# altuamSTM32_schematic.net
KiCad netlist of a schematic drawn in Altium Designer
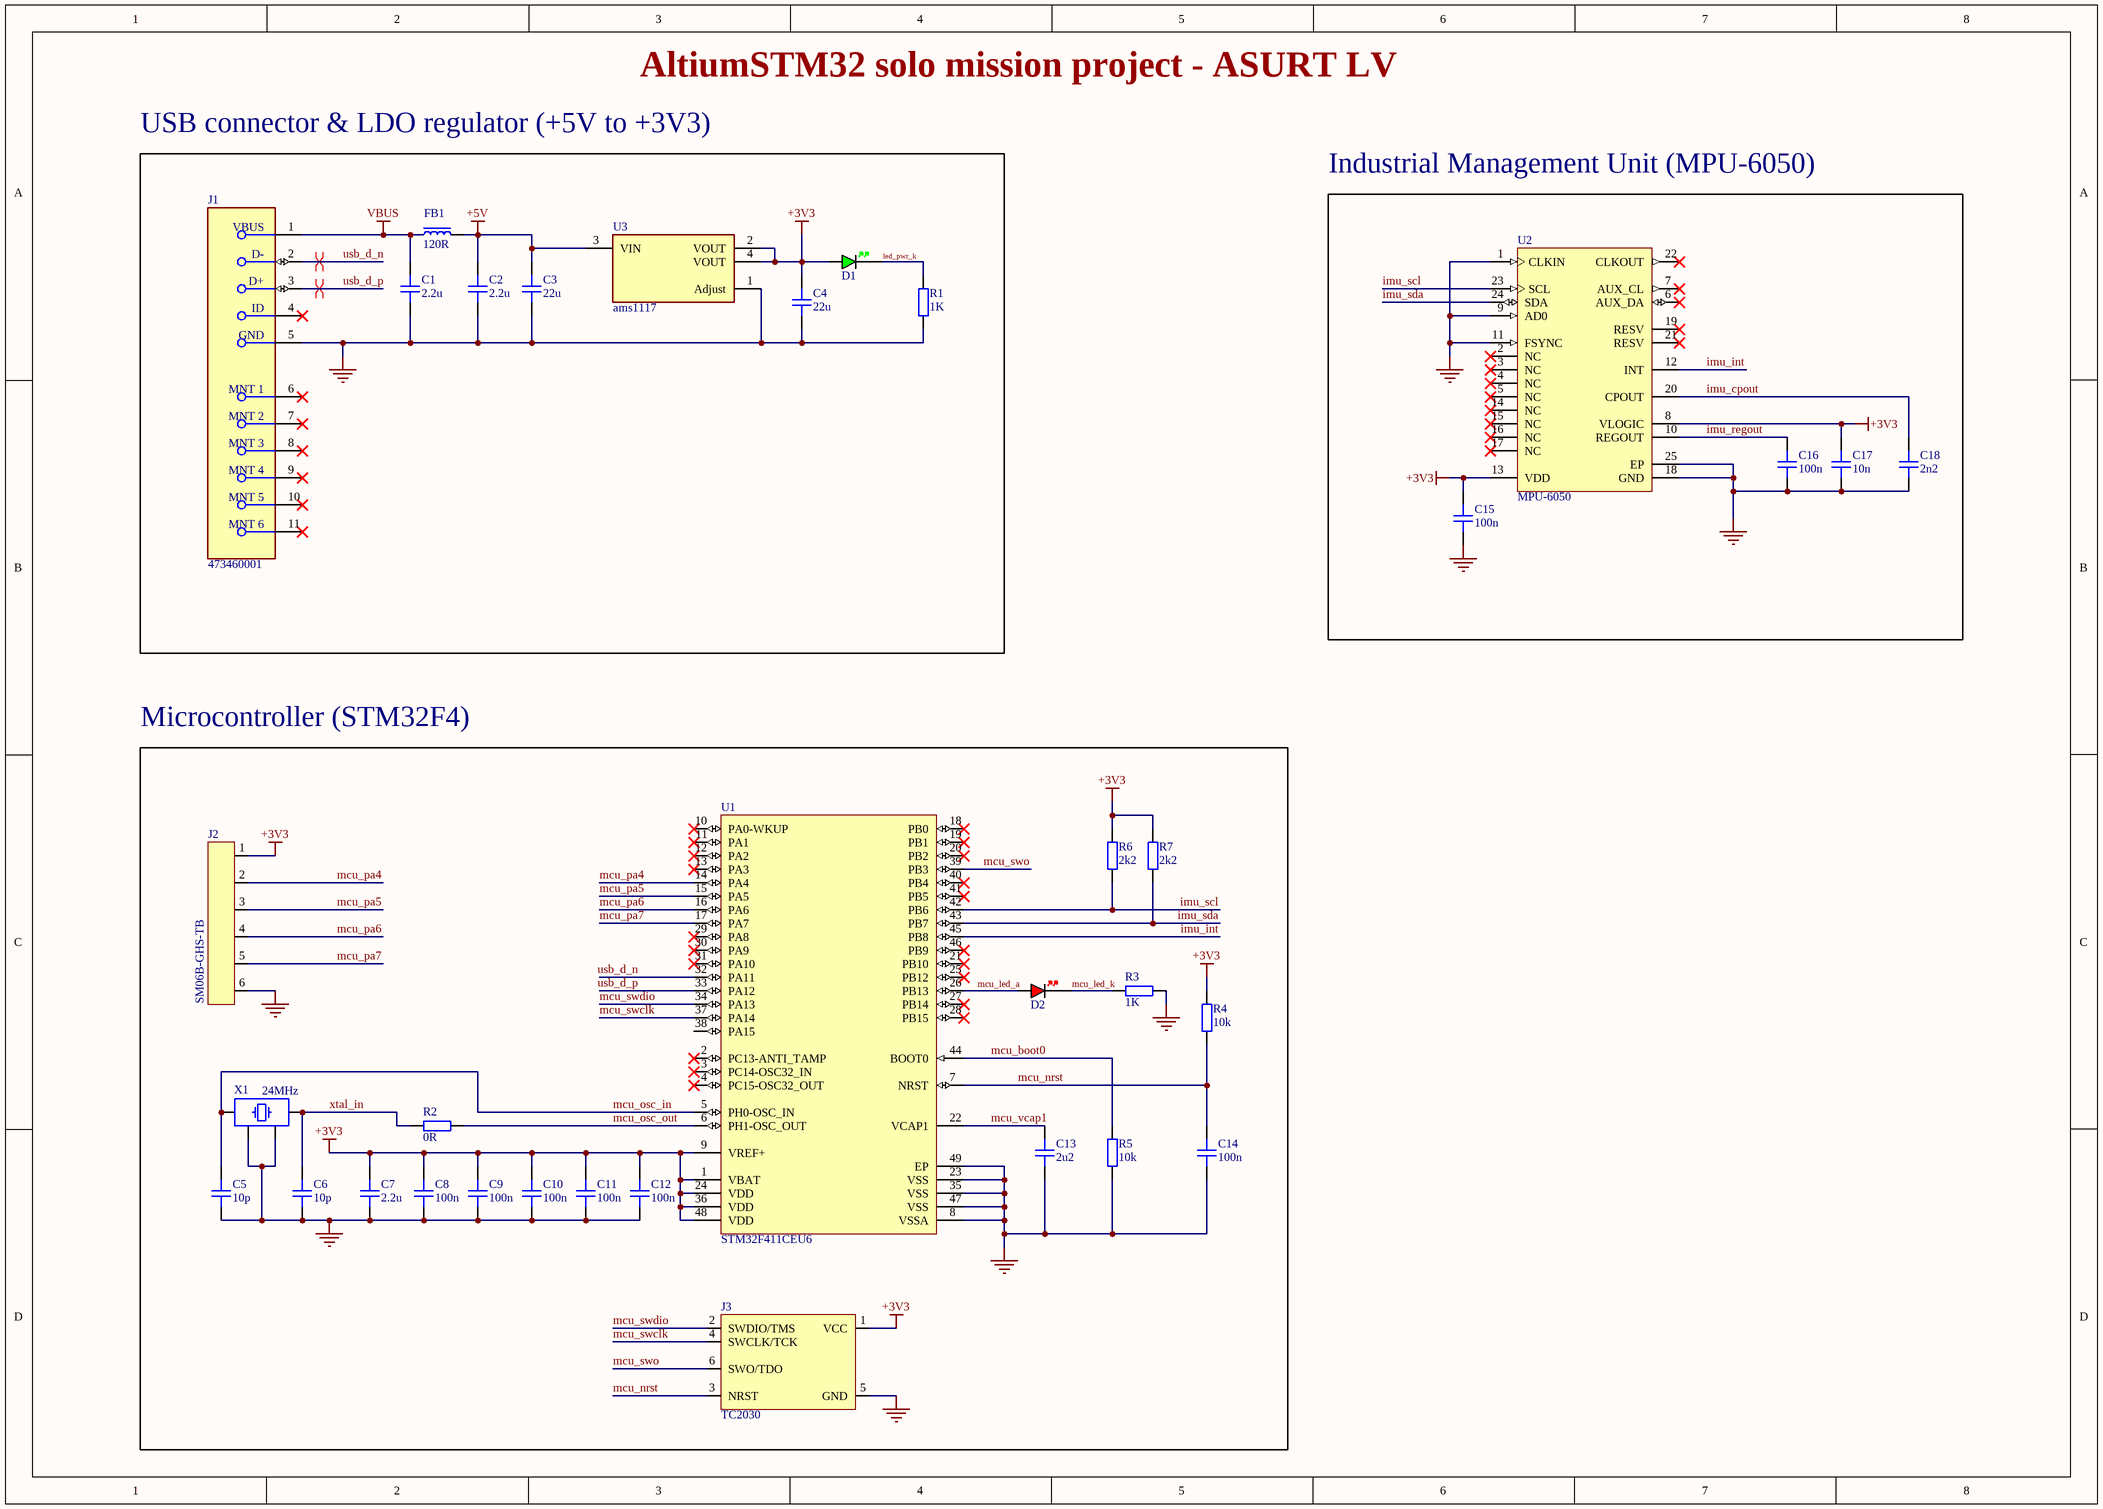
[diagram p0: altuamSTM32_schematic.SchDoc]

(export (version "E")
  (design (tool "Eeschema 10.0.6"))
  (components
    (comp (ref "C1")
      (value "2.2u")
      (footprint "CAP_0603")
      (description "Capacitor SMD 0603")
      (libsource (lib "Schematic-Lib-PhilsLab") (part "CAP_0603"))
    )
    (comp (ref "C2")
      (value "2.2u")
      (footprint "CAP_0603")
      (description "Capacitor SMD 0603")
      (libsource (lib "Schematic-Lib-PhilsLab") (part "CAP_0603"))
    )
    (comp (ref "C3")
      (value "22u")
      (footprint "CAP_0805")
      (description "Capacitor SMD 0805")
      (libsource (lib "Schematic-Lib-PhilsLab") (part "CAP_0805"))
    )
    (comp (ref "C4")
      (value "22u")
      (footprint "CAP_0805")
      (description "Capacitor SMD 0805")
      (libsource (lib "Schematic-Lib-PhilsLab") (part "CAP_0805"))
    )
    (comp (ref "C5")
      (value "10p")
      (footprint "CAP_0402")
      (description "Capacitor SMD 0402")
      (libsource (lib "Schematic-Lib-PhilsLab") (part "CAP_0402"))
    )
    (comp (ref "C6")
      (value "10p")
      (footprint "CAP_0402")
      (description "Capacitor SMD 0402")
      (libsource (lib "Schematic-Lib-PhilsLab") (part "CAP_0402"))
    )
    (comp (ref "C7")
      (value "2.2u")
      (footprint "CAP_0603")
      (description "Capacitor SMD 0603")
      (libsource (lib "Schematic-Lib-PhilsLab") (part "CAP_0603"))
    )
    (comp (ref "C8")
      (value "100n")
      (footprint "CAP_0402")
      (description "Capacitor SMD 0402")
      (libsource (lib "Schematic-Lib-PhilsLab") (part "CAP_0402"))
    )
    (comp (ref "C9")
      (value "100n")
      (footprint "CAP_0402")
      (description "Capacitor SMD 0402")
      (libsource (lib "Schematic-Lib-PhilsLab") (part "CAP_0402"))
    )
    (comp (ref "C10")
      (value "100n")
      (footprint "CAP_0402")
      (description "Capacitor SMD 0402")
      (libsource (lib "Schematic-Lib-PhilsLab") (part "CAP_0402"))
    )
    (comp (ref "C11")
      (value "100n")
      (footprint "CAP_0402")
      (description "Capacitor SMD 0402")
      (libsource (lib "Schematic-Lib-PhilsLab") (part "CAP_0402"))
    )
    (comp (ref "C12")
      (value "100n")
      (footprint "CAP_0402")
      (description "Capacitor SMD 0402")
      (libsource (lib "Schematic-Lib-PhilsLab") (part "CAP_0402"))
    )
    (comp (ref "C13")
      (value "2u2")
      (footprint "CAP_0603")
      (description "Capacitor SMD 0603")
      (libsource (lib "Schematic-Lib-PhilsLab") (part "CAP_0603"))
    )
    (comp (ref "C14")
      (value "100n")
      (footprint "CAP_0402")
      (description "Capacitor SMD 0402")
      (libsource (lib "Schematic-Lib-PhilsLab") (part "CAP_0402"))
    )
    (comp (ref "C15")
      (value "100n")
      (footprint "CAP_0402")
      (description "Capacitor SMD 0402")
      (libsource (lib "Schematic-Lib-PhilsLab") (part "CAP_0402"))
    )
    (comp (ref "C16")
      (value "100n")
      (footprint "CAP_0402")
      (description "Capacitor SMD 0402")
      (libsource (lib "Schematic-Lib-PhilsLab") (part "CAP_0402"))
    )
    (comp (ref "C17")
      (value "10n")
      (footprint "CAP_0402")
      (description "Capacitor SMD 0402")
      (libsource (lib "Schematic-Lib-PhilsLab") (part "CAP_0402"))
    )
    (comp (ref "C18")
      (value "2n2")
      (footprint "CAP_0402")
      (description "Capacitor SMD 0402")
      (libsource (lib "Schematic-Lib-PhilsLab") (part "CAP_0402"))
    )
    (comp (ref "D1")
      (value "GREEN")
      (footprint "LED_0402_GREEN")
      (description "LED 0402 GREEN SMD")
      (libsource (lib "Schematic-Lib-PhilsLab") (part "LED_0402_GREEN"))
    )
    (comp (ref "D2")
      (value "RED")
      (footprint "LED_0402_RED")
      (description "LED 0402 RED SMD")
      (libsource (lib "Schematic-Lib-PhilsLab") (part "LED_0402_RED"))
    )
    (comp (ref "FB1")
      (value "120R")
      (footprint "FB_0603")
      (description "Ferrite Bead SMD 0603")
      (libsource (lib "Schematic-Lib-PhilsLab") (part "FB_0603"))
    )
    (comp (ref "J1")
      (value "473460001")
      (footprint "FP-473460001-MFG")
      (description "USB - micro B USB 2.0 Receptacle Connector 5 Position Surface Mount, Right Angle")
      (fields (field (name "OCTOPART") "https://octopart.com/47346-0001-molex-7164928"))
      (libsource (lib "Altium Content Vault") (part "53ae1f1d9b557310b43ca686e5bb76a"))
    )
    (comp (ref "J2")
      (value "SM06B-GHS-TB")
      (footprint "SM06B-GHS-TB")
      (description "Header Connector 6 Position 1.25MM Pitch SMD Horizontal JST GH")
      (fields (field (name "MANUFACTURER") "JST"))
      (libsource (lib "Schematic-Lib-PhilsLab") (part "SM06B-GHS-TB"))
    )
    (comp (ref "J3")
      (value "TC2030")
      (footprint "TC2030-FP")
      (description "Tag-Connect No-Solder SWD Debug Connector DO NOT PLACE")
      (fields (field (name "MANUFACTURER") "Tag-Connect"))
      (libsource (lib "Schematic-Lib-PhilsLab") (part "TC2030"))
    )
    (comp (ref "R1")
      (value "1K")
      (footprint "RES_0402")
      (description "Resistor SMD 0402")
      (libsource (lib "Schematic-Lib-PhilsLab") (part "RES_0402"))
    )
    (comp (ref "R2")
      (value "0R")
      (footprint "RES_0402")
      (description "Resistor SMD 0402")
      (libsource (lib "Schematic-Lib-PhilsLab") (part "RES_0402"))
    )
    (comp (ref "R3")
      (value "1K")
      (footprint "RES_0402")
      (description "Resistor SMD 0402")
      (libsource (lib "Schematic-Lib-PhilsLab") (part "RES_0402"))
    )
    (comp (ref "R4")
      (value "10k")
      (footprint "RES_0402")
      (description "Resistor SMD 0402")
      (libsource (lib "Schematic-Lib-PhilsLab") (part "RES_0402"))
    )
    (comp (ref "R5")
      (value "10k")
      (footprint "RES_0402")
      (description "Resistor SMD 0402")
      (libsource (lib "Schematic-Lib-PhilsLab") (part "RES_0402"))
    )
    (comp (ref "R6")
      (value "2k2")
      (footprint "RES_0402")
      (description "Resistor SMD 0402")
      (libsource (lib "Schematic-Lib-PhilsLab") (part "RES_0402"))
    )
    (comp (ref "R7")
      (value "2k2")
      (footprint "RES_0402")
      (description "Resistor SMD 0402")
      (libsource (lib "Schematic-Lib-PhilsLab") (part "RES_0402"))
    )
    (comp (ref "U1")
      (value "STM32F411CEU6")
      (footprint "STM-UFQFPN48_L")
      (libsource (lib "Altium Content Vault") (part "MC-ARM-STM32F411-UFQFPN48"))
    )
    (comp (ref "U2")
      (value "MPU-6050")
      (footprint "IS-QFN-24_V")
      (fields (field (name "MANUFACTURER") "InvenSense"))
      (libsource (lib "Altium Content Vault") (part "IS-MPU-6050-QFN-24"))
    )
    (comp (ref "U3")
      (value "ams1117")
      (footprint "FP-ams1117-IPC_C")
      (description "1A LOW DROPOUT VOLTAGE REGULATOR")
      (libsource (lib "Altium Content Vault") (part "59ad430b93a2c51b3e6ee7c3b069677"))
    )
    (comp (ref "X1")
      (value "24MHz")
      (footprint "XTAL_3225")
      (description "Crystal SMD 24MHz 10PPM 7pF 3225")
      (fields
        (field (name "MANUFACTURER") "Epson")
        (field (name "MANUFACTURER PART NUMBER") "TSX-3225 24.0000MF15X-AC")
      )
      (libsource (lib "Schematic-Lib-PhilsLab") (part "TSX-3225_24.0000MF15X-AC"))
    )
  )
  (nets
    (net (code "1") (name "+3V3") (class "Default")
      (node (ref "C10") (pin "2") (pinfunction "2_2") (pintype "passive"))
      (node (ref "C11") (pin "2") (pinfunction "2_2") (pintype "passive"))
      (node (ref "C12") (pin "2") (pinfunction "2_2") (pintype "passive"))
      (node (ref "C15") (pin "2") (pinfunction "2_2") (pintype "passive"))
      (node (ref "C17") (pin "2") (pinfunction "2_2") (pintype "passive"))
      (node (ref "C4") (pin "2") (pinfunction "2_2") (pintype "passive"))
      (node (ref "C7") (pin "2") (pinfunction "2_2") (pintype "passive"))
      (node (ref "C8") (pin "2") (pinfunction "2_2") (pintype "passive"))
      (node (ref "C9") (pin "2") (pinfunction "2_2") (pintype "passive"))
      (node (ref "D1") (pin "A") (pinfunction "A_A") (pintype "passive"))
      (node (ref "J2") (pin "1") (pinfunction "1_1") (pintype "passive"))
      (node (ref "J3") (pin "1") (pinfunction "VCC_1") (pintype "passive"))
      (node (ref "R4") (pin "2") (pinfunction "2_2") (pintype "passive"))
      (node (ref "R6") (pin "2") (pinfunction "2_2") (pintype "passive"))
      (node (ref "R7") (pin "2") (pinfunction "2_2") (pintype "passive"))
      (node (ref "U1") (pin "1") (pinfunction "VBAT_1") (pintype "power_in"))
      (node (ref "U1") (pin "24") (pinfunction "VDD_24") (pintype "power_in"))
      (node (ref "U1") (pin "36") (pinfunction "VDD_36") (pintype "power_in"))
      (node (ref "U1") (pin "48") (pinfunction "VDD_48") (pintype "power_in"))
      (node (ref "U1") (pin "9") (pinfunction "VREF+_9") (pintype "power_in"))
      (node (ref "U2") (pin "13") (pinfunction "VDD_13") (pintype "power_in"))
      (node (ref "U2") (pin "8") (pinfunction "VLOGIC_8") (pintype "power_in"))
      (node (ref "U3") (pin "2") (pinfunction "VOUT_2") (pintype "passive"))
      (node (ref "U3") (pin "4") (pinfunction "VOUT_4") (pintype "passive"))
    )
    (net (code "2") (name "+5V") (class "Default")
      (node (ref "C2") (pin "2") (pinfunction "2_2") (pintype "passive"))
      (node (ref "C3") (pin "2") (pinfunction "2_2") (pintype "passive"))
      (node (ref "FB1") (pin "2") (pinfunction "2_2") (pintype "passive"))
      (node (ref "U3") (pin "3") (pinfunction "VIN_3") (pintype "power_in"))
    )
    (net (code "3") (name "/imu_cpout") (class "Default")
      (node (ref "C18") (pin "2") (pinfunction "2_2") (pintype "passive"))
      (node (ref "U2") (pin "20") (pinfunction "CPOUT_20") (pintype "passive"))
    )
    (net (code "4") (name "/imu_int") (class "Default")
      (node (ref "U1") (pin "45") (pinfunction "PB8_45") (pintype "bidirectional"))
      (node (ref "U2") (pin "12") (pinfunction "INT_12") (pintype "open_collector"))
    )
    (net (code "5") (name "/imu_regout") (class "Default")
      (node (ref "C16") (pin "2") (pinfunction "2_2") (pintype "passive"))
      (node (ref "U2") (pin "10") (pinfunction "REGOUT_10") (pintype "passive"))
    )
    (net (code "6") (name "/imu_scl") (class "Default")
      (node (ref "R6") (pin "1") (pinfunction "1_1") (pintype "passive"))
      (node (ref "U1") (pin "42") (pinfunction "PB6_42") (pintype "bidirectional"))
      (node (ref "U2") (pin "23") (pinfunction "SCL_23") (pintype "input"))
    )
    (net (code "7") (name "/imu_sda") (class "Default")
      (node (ref "R7") (pin "1") (pinfunction "1_1") (pintype "passive"))
      (node (ref "U1") (pin "43") (pinfunction "PB7_43") (pintype "bidirectional"))
      (node (ref "U2") (pin "24") (pinfunction "SDA_24") (pintype "bidirectional"))
    )
    (net (code "8") (name "/led_pwr_k") (class "Default")
      (node (ref "D1") (pin "K") (pinfunction "K_K") (pintype "passive"))
      (node (ref "R1") (pin "2") (pinfunction "2_2") (pintype "passive"))
    )
    (net (code "9") (name "/mcu_boot0") (class "Default")
      (node (ref "R5") (pin "2") (pinfunction "2_2") (pintype "passive"))
      (node (ref "U1") (pin "44") (pinfunction "BOOT0_44") (pintype "input"))
    )
    (net (code "10") (name "/mcu_led_a") (class "Default")
      (node (ref "D2") (pin "A") (pinfunction "A_A") (pintype "passive"))
      (node (ref "U1") (pin "26") (pinfunction "PB13_26") (pintype "bidirectional"))
    )
    (net (code "11") (name "/mcu_led_k") (class "Default")
      (node (ref "D2") (pin "K") (pinfunction "K_K") (pintype "passive"))
      (node (ref "R3") (pin "2") (pinfunction "2_2") (pintype "passive"))
    )
    (net (code "12") (name "/mcu_nrst") (class "Default")
      (node (ref "C14") (pin "2") (pinfunction "2_2") (pintype "passive"))
      (node (ref "J3") (pin "3") (pinfunction "NRST_3") (pintype "passive"))
      (node (ref "R4") (pin "1") (pinfunction "1_1") (pintype "passive"))
      (node (ref "U1") (pin "7") (pinfunction "NRST_7") (pintype "bidirectional"))
    )
    (net (code "13") (name "/mcu_osc_in") (class "Default")
      (node (ref "C5") (pin "2") (pinfunction "2_2") (pintype "passive"))
      (node (ref "U1") (pin "5") (pinfunction "PH0-OSC_IN_5") (pintype "bidirectional"))
      (node (ref "X1") (pin "1") (pinfunction "1_1") (pintype "passive"))
    )
    (net (code "14") (name "/mcu_osc_out") (class "Default")
      (node (ref "R2") (pin "2") (pinfunction "2_2") (pintype "passive"))
      (node (ref "U1") (pin "6") (pinfunction "PH1-OSC_OUT_6") (pintype "bidirectional"))
    )
    (net (code "15") (name "/mcu_pa4") (class "Default")
      (node (ref "J2") (pin "2") (pinfunction "2_2") (pintype "passive"))
      (node (ref "U1") (pin "14") (pinfunction "PA4_14") (pintype "bidirectional"))
    )
    (net (code "16") (name "/mcu_pa5") (class "Default")
      (node (ref "J2") (pin "3") (pinfunction "3_3") (pintype "passive"))
      (node (ref "U1") (pin "15") (pinfunction "PA5_15") (pintype "bidirectional"))
    )
    (net (code "17") (name "/mcu_pa6") (class "Default")
      (node (ref "J2") (pin "4") (pinfunction "4_4") (pintype "passive"))
      (node (ref "U1") (pin "16") (pinfunction "PA6_16") (pintype "bidirectional"))
    )
    (net (code "18") (name "/mcu_pa7") (class "Default")
      (node (ref "J2") (pin "5") (pinfunction "5_5") (pintype "passive"))
      (node (ref "U1") (pin "17") (pinfunction "PA7_17") (pintype "bidirectional"))
    )
    (net (code "19") (name "/mcu_swclk") (class "Default")
      (node (ref "J3") (pin "4") (pinfunction "SWCLK/TCK_4") (pintype "passive"))
      (node (ref "U1") (pin "37") (pinfunction "PA14_37") (pintype "bidirectional"))
    )
    (net (code "20") (name "/mcu_swdio") (class "Default")
      (node (ref "J3") (pin "2") (pinfunction "SWDIO/TMS_2") (pintype "passive"))
      (node (ref "U1") (pin "34") (pinfunction "PA13_34") (pintype "bidirectional"))
    )
    (net (code "21") (name "/mcu_swo") (class "Default")
      (node (ref "J3") (pin "6") (pinfunction "SWO/TDO_6") (pintype "passive"))
      (node (ref "U1") (pin "39") (pinfunction "PB3_39") (pintype "bidirectional"))
    )
    (net (code "22") (name "/mcu_vcap1") (class "Default")
      (node (ref "C13") (pin "2") (pinfunction "2_2") (pintype "passive"))
      (node (ref "U1") (pin "22") (pinfunction "VCAP1_22") (pintype "passive"))
    )
    (net (code "23") (name "/usb_d_n") (class "Default")
      (node (ref "J1") (pin "2") (pinfunction "D-_2") (pintype "bidirectional"))
      (node (ref "U1") (pin "32") (pinfunction "PA11_32") (pintype "bidirectional"))
    )
    (net (code "24") (name "/usb_d_p") (class "Default")
      (node (ref "J1") (pin "3") (pinfunction "D+_3") (pintype "bidirectional"))
      (node (ref "U1") (pin "33") (pinfunction "PA12_33") (pintype "bidirectional"))
    )
    (net (code "25") (name "/xtal_in") (class "Default")
      (node (ref "C6") (pin "2") (pinfunction "2_2") (pintype "passive"))
      (node (ref "R2") (pin "1") (pinfunction "1_1") (pintype "passive"))
      (node (ref "X1") (pin "3") (pinfunction "3_3") (pintype "passive"))
    )
    (net (code "26") (name "GND") (class "Default")
      (node (ref "C1") (pin "1") (pinfunction "1_1") (pintype "passive"))
      (node (ref "C10") (pin "1") (pinfunction "1_1") (pintype "passive"))
      (node (ref "C11") (pin "1") (pinfunction "1_1") (pintype "passive"))
      (node (ref "C12") (pin "1") (pinfunction "1_1") (pintype "passive"))
      (node (ref "C13") (pin "1") (pinfunction "1_1") (pintype "passive"))
      (node (ref "C14") (pin "1") (pinfunction "1_1") (pintype "passive"))
      (node (ref "C15") (pin "1") (pinfunction "1_1") (pintype "passive"))
      (node (ref "C16") (pin "1") (pinfunction "1_1") (pintype "passive"))
      (node (ref "C17") (pin "1") (pinfunction "1_1") (pintype "passive"))
      (node (ref "C18") (pin "1") (pinfunction "1_1") (pintype "passive"))
      (node (ref "C2") (pin "1") (pinfunction "1_1") (pintype "passive"))
      (node (ref "C3") (pin "1") (pinfunction "1_1") (pintype "passive"))
      (node (ref "C4") (pin "1") (pinfunction "1_1") (pintype "passive"))
      (node (ref "C5") (pin "1") (pinfunction "1_1") (pintype "passive"))
      (node (ref "C6") (pin "1") (pinfunction "1_1") (pintype "passive"))
      (node (ref "C7") (pin "1") (pinfunction "1_1") (pintype "passive"))
      (node (ref "C8") (pin "1") (pinfunction "1_1") (pintype "passive"))
      (node (ref "C9") (pin "1") (pinfunction "1_1") (pintype "passive"))
      (node (ref "J1") (pin "5") (pinfunction "GND_5") (pintype "power_in"))
      (node (ref "J2") (pin "6") (pinfunction "6_6") (pintype "passive"))
      (node (ref "J3") (pin "5") (pinfunction "GND_5") (pintype "passive"))
      (node (ref "R1") (pin "1") (pinfunction "1_1") (pintype "passive"))
      (node (ref "R3") (pin "1") (pinfunction "1_1") (pintype "passive"))
      (node (ref "R5") (pin "1") (pinfunction "1_1") (pintype "passive"))
      (node (ref "U1") (pin "23") (pinfunction "VSS_23") (pintype "power_in"))
      (node (ref "U1") (pin "35") (pinfunction "VSS_35") (pintype "power_in"))
      (node (ref "U1") (pin "47") (pinfunction "VSS_47") (pintype "power_in"))
      (node (ref "U1") (pin "49") (pinfunction "EP_49") (pintype "power_in"))
      (node (ref "U1") (pin "8") (pinfunction "VSSA_8") (pintype "power_in"))
      (node (ref "U2") (pin "1") (pinfunction "CLKIN_1") (pintype "input"))
      (node (ref "U2") (pin "11") (pinfunction "FSYNC_11") (pintype "input"))
      (node (ref "U2") (pin "18") (pinfunction "GND_18") (pintype "power_in"))
      (node (ref "U2") (pin "25") (pinfunction "EP_25") (pintype "power_in"))
      (node (ref "U2") (pin "9") (pinfunction "AD0_9") (pintype "input"))
      (node (ref "U3") (pin "1") (pinfunction "Adjust_1") (pintype "passive"))
      (node (ref "X1") (pin "2") (pinfunction "2_2") (pintype "passive"))
      (node (ref "X1") (pin "4") (pinfunction "4_4") (pintype "passive"))
    )
    (net (code "27") (name "VBUS") (class "Default")
      (node (ref "C1") (pin "2") (pinfunction "2_2") (pintype "passive"))
      (node (ref "FB1") (pin "1") (pinfunction "1_1") (pintype "passive"))
      (node (ref "J1") (pin "1") (pinfunction "VBUS_1") (pintype "power_in"))
    )
    (net (code "28") (name "unconnected-(J1-ID-Pad4)") (class "Default")
      (node (ref "J1") (pin "4") (pinfunction "ID_4") (pintype "passive+no_connect"))
    )
    (net (code "29") (name "unconnected-(J1-MNT_1-Pad6)") (class "Default")
      (node (ref "J1") (pin "6") (pinfunction "MNT_1_6") (pintype "passive+no_connect"))
    )
    (net (code "30") (name "unconnected-(J1-MNT_2-Pad7)") (class "Default")
      (node (ref "J1") (pin "7") (pinfunction "MNT_2_7") (pintype "passive+no_connect"))
    )
    (net (code "31") (name "unconnected-(J1-MNT_3-Pad8)") (class "Default")
      (node (ref "J1") (pin "8") (pinfunction "MNT_3_8") (pintype "passive+no_connect"))
    )
    (net (code "32") (name "unconnected-(J1-MNT_4-Pad9)") (class "Default")
      (node (ref "J1") (pin "9") (pinfunction "MNT_4_9") (pintype "passive+no_connect"))
    )
    (net (code "33") (name "unconnected-(J1-MNT_5-Pad10)") (class "Default")
      (node (ref "J1") (pin "10") (pinfunction "MNT_5_10") (pintype "passive+no_connect"))
    )
    (net (code "34") (name "unconnected-(J1-MNT_6-Pad11)") (class "Default")
      (node (ref "J1") (pin "11") (pinfunction "MNT_6_11") (pintype "passive+no_connect"))
    )
    (net (code "35") (name "unconnected-(U1-PA0-WKUP-Pad10)") (class "Default")
      (node (ref "U1") (pin "10") (pinfunction "PA0-WKUP_10") (pintype "bidirectional+no_connect"))
    )
    (net (code "36") (name "unconnected-(U1-PA1-Pad11)") (class "Default")
      (node (ref "U1") (pin "11") (pinfunction "PA1_11") (pintype "bidirectional+no_connect"))
    )
    (net (code "37") (name "unconnected-(U1-PA2-Pad12)") (class "Default")
      (node (ref "U1") (pin "12") (pinfunction "PA2_12") (pintype "bidirectional+no_connect"))
    )
    (net (code "38") (name "unconnected-(U1-PA3-Pad13)") (class "Default")
      (node (ref "U1") (pin "13") (pinfunction "PA3_13") (pintype "bidirectional+no_connect"))
    )
    (net (code "39") (name "unconnected-(U1-PA8-Pad29)") (class "Default")
      (node (ref "U1") (pin "29") (pinfunction "PA8_29") (pintype "bidirectional+no_connect"))
    )
    (net (code "40") (name "unconnected-(U1-PA9-Pad30)") (class "Default")
      (node (ref "U1") (pin "30") (pinfunction "PA9_30") (pintype "bidirectional+no_connect"))
    )
    (net (code "41") (name "unconnected-(U1-PA10-Pad31)") (class "Default")
      (node (ref "U1") (pin "31") (pinfunction "PA10_31") (pintype "bidirectional+no_connect"))
    )
    (net (code "42") (name "unconnected-(U1-PA15-Pad38)") (class "Default")
      (node (ref "U1") (pin "38") (pinfunction "PA15_38") (pintype "bidirectional"))
    )
    (net (code "43") (name "unconnected-(U1-PB0-Pad18)") (class "Default")
      (node (ref "U1") (pin "18") (pinfunction "PB0_18") (pintype "bidirectional+no_connect"))
    )
    (net (code "44") (name "unconnected-(U1-PB1-Pad19)") (class "Default")
      (node (ref "U1") (pin "19") (pinfunction "PB1_19") (pintype "bidirectional+no_connect"))
    )
    (net (code "45") (name "unconnected-(U1-PB2-Pad20)") (class "Default")
      (node (ref "U1") (pin "20") (pinfunction "PB2_20") (pintype "bidirectional+no_connect"))
    )
    (net (code "46") (name "unconnected-(U1-PB4-Pad40)") (class "Default")
      (node (ref "U1") (pin "40") (pinfunction "PB4_40") (pintype "bidirectional+no_connect"))
    )
    (net (code "47") (name "unconnected-(U1-PB5-Pad41)") (class "Default")
      (node (ref "U1") (pin "41") (pinfunction "PB5_41") (pintype "bidirectional+no_connect"))
    )
    (net (code "48") (name "unconnected-(U1-PB9-Pad46)") (class "Default")
      (node (ref "U1") (pin "46") (pinfunction "PB9_46") (pintype "bidirectional+no_connect"))
    )
    (net (code "49") (name "unconnected-(U1-PB10-Pad21)") (class "Default")
      (node (ref "U1") (pin "21") (pinfunction "PB10_21") (pintype "bidirectional+no_connect"))
    )
    (net (code "50") (name "unconnected-(U1-PB12-Pad25)") (class "Default")
      (node (ref "U1") (pin "25") (pinfunction "PB12_25") (pintype "bidirectional+no_connect"))
    )
    (net (code "51") (name "unconnected-(U1-PB14-Pad27)") (class "Default")
      (node (ref "U1") (pin "27") (pinfunction "PB14_27") (pintype "bidirectional+no_connect"))
    )
    (net (code "52") (name "unconnected-(U1-PB15-Pad28)") (class "Default")
      (node (ref "U1") (pin "28") (pinfunction "PB15_28") (pintype "bidirectional+no_connect"))
    )
    (net (code "53") (name "unconnected-(U1-PC13-ANTI_TAMP-Pad2)") (class "Default")
      (node (ref "U1") (pin "2") (pinfunction "PC13-ANTI_TAMP_2") (pintype "bidirectional+no_connect"))
    )
    (net (code "54") (name "unconnected-(U1-PC14-OSC32_IN-Pad3)") (class "Default")
      (node (ref "U1") (pin "3") (pinfunction "PC14-OSC32_IN_3") (pintype "bidirectional+no_connect"))
    )
    (net (code "55") (name "unconnected-(U1-PC15-OSC32_OUT-Pad4)") (class "Default")
      (node (ref "U1") (pin "4") (pinfunction "PC15-OSC32_OUT_4") (pintype "bidirectional+no_connect"))
    )
    (net (code "56") (name "unconnected-(U2-AUX_CL-Pad7)") (class "Default")
      (node (ref "U2") (pin "7") (pinfunction "AUX_CL_7") (pintype "output+no_connect"))
    )
    (net (code "57") (name "unconnected-(U2-AUX_DA-Pad6)") (class "Default")
      (node (ref "U2") (pin "6") (pinfunction "AUX_DA_6") (pintype "bidirectional+no_connect"))
    )
    (net (code "58") (name "unconnected-(U2-CLKOUT-Pad22)") (class "Default")
      (node (ref "U2") (pin "22") (pinfunction "CLKOUT_22") (pintype "output+no_connect"))
    )
    (net (code "59") (name "unconnected-(U2-NC-Pad2)") (class "Default")
      (node (ref "U2") (pin "2") (pinfunction "NC_2") (pintype "passive+no_connect"))
    )
    (net (code "60") (name "unconnected-(U2-NC-Pad3)") (class "Default")
      (node (ref "U2") (pin "3") (pinfunction "NC_3") (pintype "passive+no_connect"))
    )
    (net (code "61") (name "unconnected-(U2-NC-Pad4)") (class "Default")
      (node (ref "U2") (pin "4") (pinfunction "NC_4") (pintype "passive+no_connect"))
    )
    (net (code "62") (name "unconnected-(U2-NC-Pad5)") (class "Default")
      (node (ref "U2") (pin "5") (pinfunction "NC_5") (pintype "passive+no_connect"))
    )
    (net (code "63") (name "unconnected-(U2-NC-Pad14)") (class "Default")
      (node (ref "U2") (pin "14") (pinfunction "NC_14") (pintype "passive+no_connect"))
    )
    (net (code "64") (name "unconnected-(U2-NC-Pad15)") (class "Default")
      (node (ref "U2") (pin "15") (pinfunction "NC_15") (pintype "passive+no_connect"))
    )
    (net (code "65") (name "unconnected-(U2-NC-Pad16)") (class "Default")
      (node (ref "U2") (pin "16") (pinfunction "NC_16") (pintype "passive+no_connect"))
    )
    (net (code "66") (name "unconnected-(U2-NC-Pad17)") (class "Default")
      (node (ref "U2") (pin "17") (pinfunction "NC_17") (pintype "passive+no_connect"))
    )
    (net (code "67") (name "unconnected-(U2-RESV-Pad19)") (class "Default")
      (node (ref "U2") (pin "19") (pinfunction "RESV_19") (pintype "passive+no_connect"))
    )
    (net (code "68") (name "unconnected-(U2-RESV-Pad21)") (class "Default")
      (node (ref "U2") (pin "21") (pinfunction "RESV_21") (pintype "passive+no_connect"))
    )
  )
)
